# old_kick_line.net
KiCad netlist of a schematic drawn in EAGLE
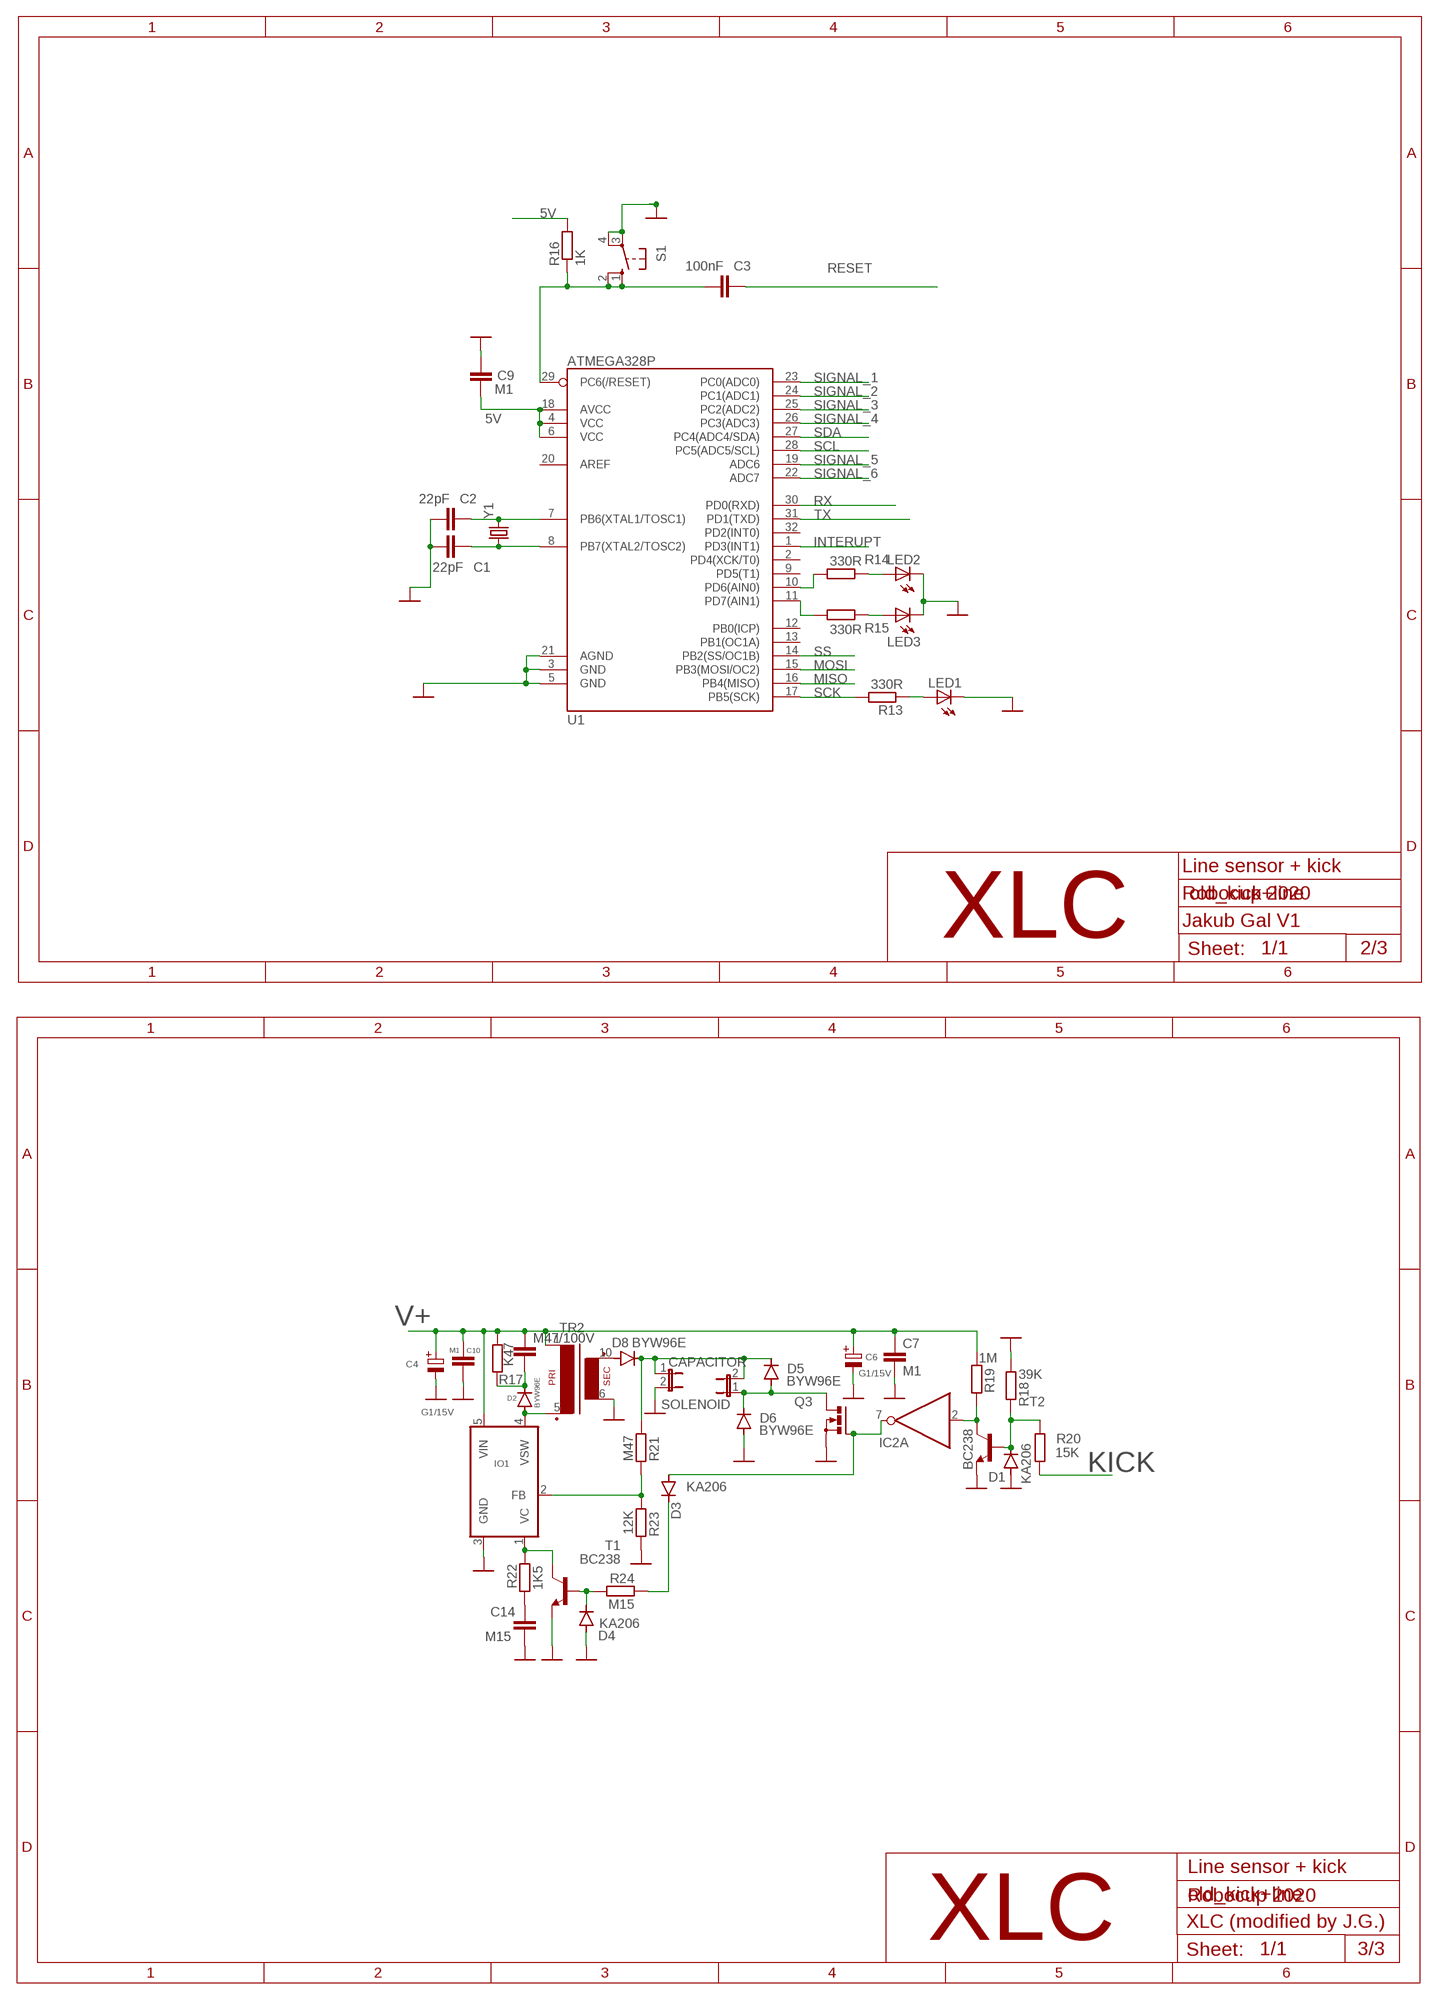
[diagram p0: schematic, sheet 1, part 1 of 2]
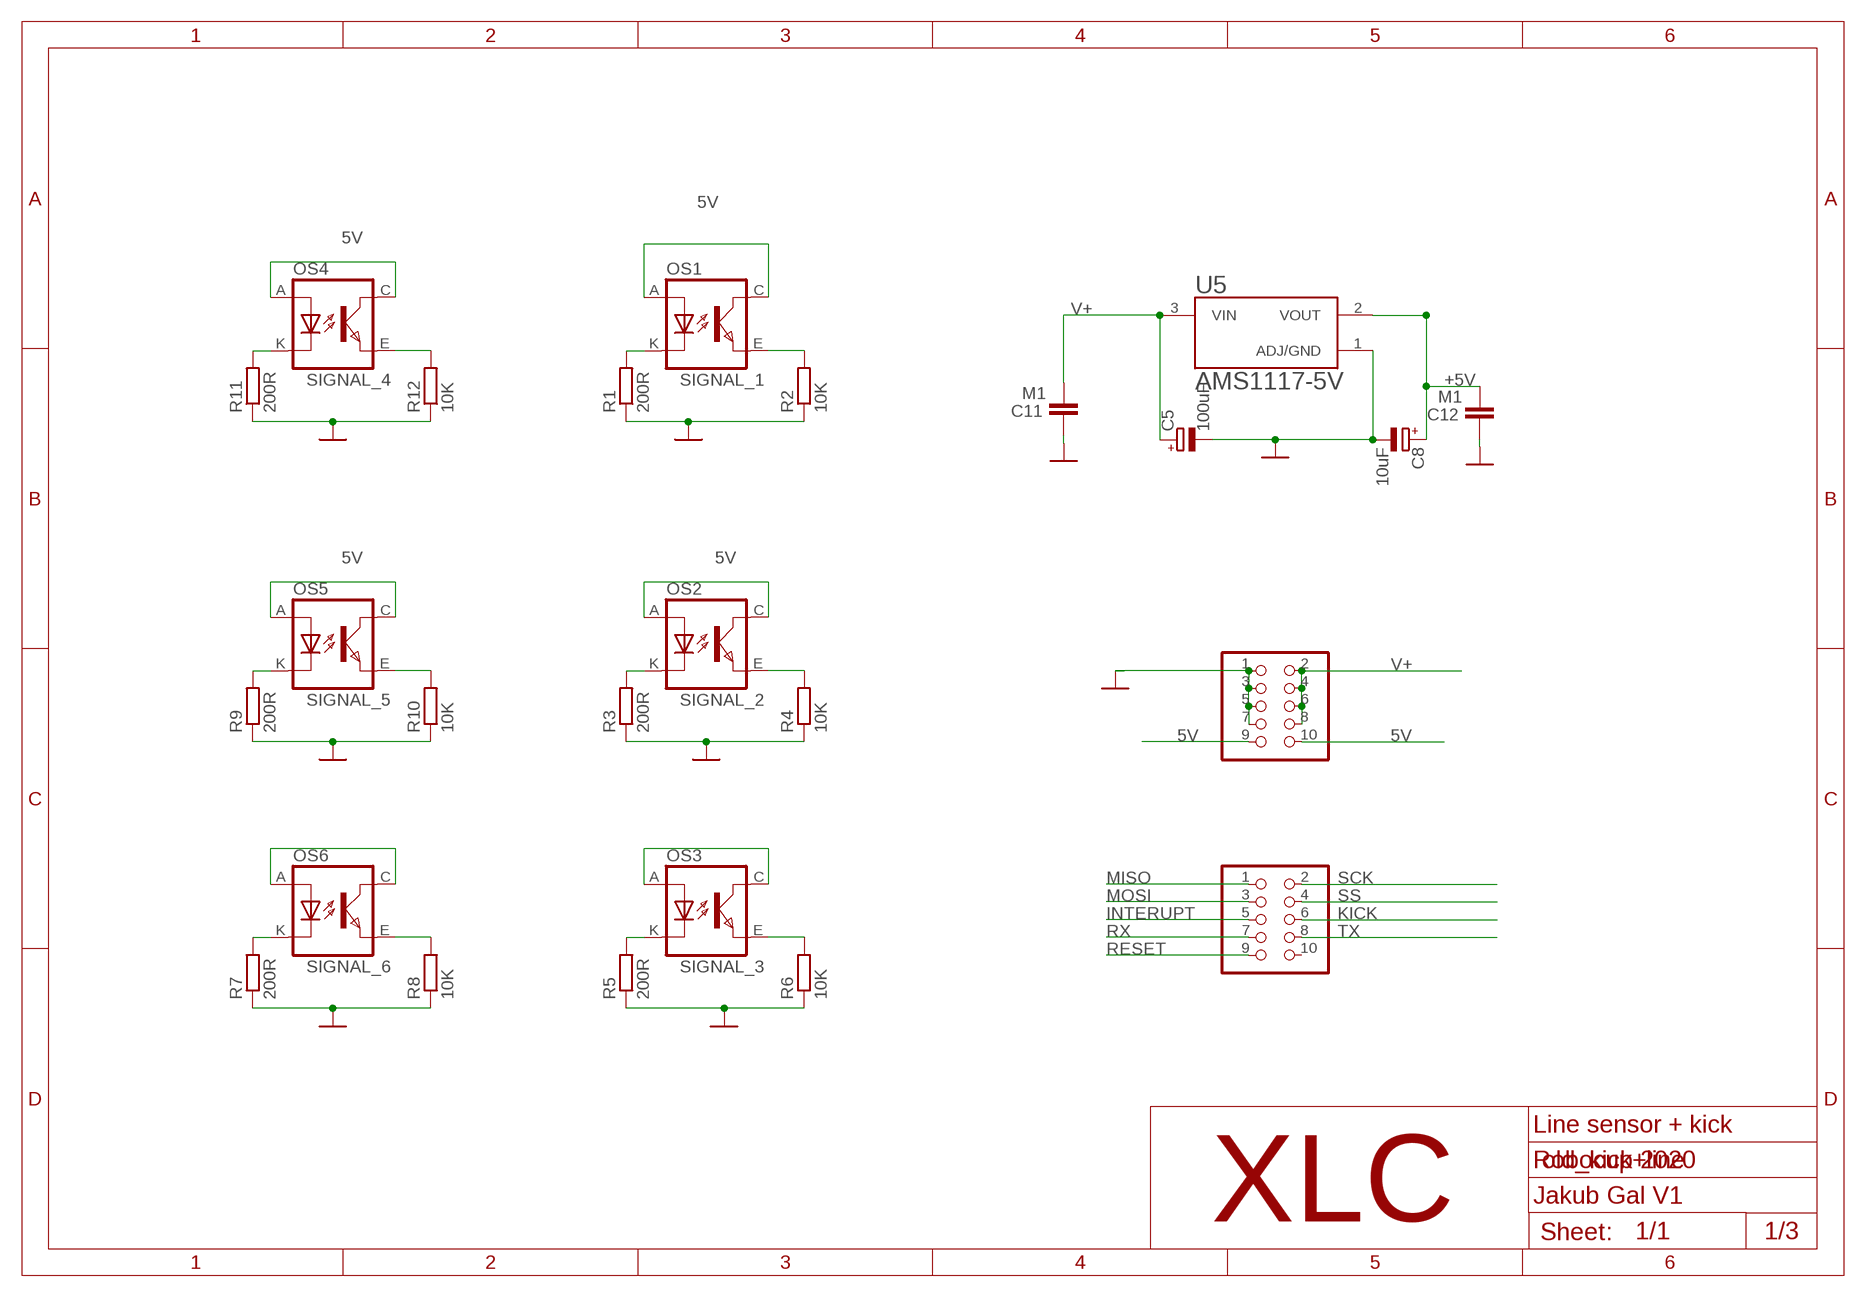
[diagram p1: schematic, sheet 1, part 2 of 2]

(export (version "E")
  (design (tool "Eeschema 10.0.6"))
  (components
    (comp (ref "C1")
      (value "22pF")
      (footprint "eagle-import:C0603")
      (libsource (lib "eagle-import") (part "C-EUC0603"))
    )
    (comp (ref "C2")
      (value "22pF")
      (footprint "eagle-import:C0603")
      (libsource (lib "eagle-import") (part "C-EUC0603"))
    )
    (comp (ref "C3")
      (value "100nF")
      (footprint "eagle-import:C0603")
      (libsource (lib "eagle-import") (part "C-EUC0603"))
    )
    (comp (ref "C4")
      (value "G1/15V")
      (footprint "eagle-import:E-2,5_7-RAD")
      (libsource (lib "eagle-import") (part "KOND-ELEKT-2,5/7"))
    )
    (comp (ref "C5")
      (value "100uF")
      (footprint "eagle-import:UD-6,3X7,7_NICHICON")
      (libsource (lib "eagle-import") (part "CPOL-EUUD-6,3X7,7"))
    )
    (comp (ref "C6")
      (value "G1/15V")
      (footprint "eagle-import:E-2,5_7-RAD")
      (libsource (lib "eagle-import") (part "KOND-ELEKT-2,5/7"))
    )
    (comp (ref "C7")
      (value "M1")
      (footprint "eagle-import:C0805K")
      (libsource (lib "eagle-import") (part "resistor_C-EUC0805K"))
    )
    (comp (ref "C8")
      (value "10uF")
      (footprint "eagle-import:UD-4X5,8_NICHICON")
      (libsource (lib "eagle-import") (part "CPOL-EUUD-4X5,8"))
    )
    (comp (ref "C9")
      (value "M1")
      (footprint "eagle-import:C0603")
      (libsource (lib "eagle-import") (part "C-EUC0603"))
    )
    (comp (ref "C10")
      (value "M1")
      (footprint "eagle-import:C0805K")
      (libsource (lib "eagle-import") (part "resistor_C-EUC0805K"))
    )
    (comp (ref "C11")
      (value "M1")
      (footprint "eagle-import:C0603")
      (libsource (lib "eagle-import") (part "C-EUC0603"))
    )
    (comp (ref "C12")
      (value "M1")
      (footprint "eagle-import:C0603")
      (libsource (lib "eagle-import") (part "C-EUC0603"))
    )
    (comp (ref "C14")
      (value "M15")
      (footprint "eagle-import:C0805K")
      (libsource (lib "eagle-import") (part "resistor_C-EUC0805K"))
    )
    (comp (ref "CAPACITOR")
      (value "JP1E")
      (footprint "eagle-import:JP1")
      (libsource (lib "eagle-import") (part "JP1E"))
    )
    (comp (ref "D1")
      (value "KA206")
      (footprint "eagle-import:D-7.5")
      (libsource (lib "eagle-import") (part "DIODE-D-7.5"))
    )
    (comp (ref "D2")
      (value "BYW96E")
      (footprint "eagle-import:SOD64-10")
      (libsource (lib "eagle-import") (part "BYW96"))
    )
    (comp (ref "D3")
      (value "KA206")
      (footprint "eagle-import:D-7.5")
      (libsource (lib "eagle-import") (part "DIODE-D-7.5"))
    )
    (comp (ref "D4")
      (value "KA206")
      (footprint "eagle-import:D-7.5")
      (libsource (lib "eagle-import") (part "DIODE-D-7.5"))
    )
    (comp (ref "D5")
      (value "BYW96E")
      (footprint "eagle-import:SOD64-10")
      (libsource (lib "eagle-import") (part "BYW96"))
    )
    (comp (ref "D6")
      (value "BYW96E")
      (footprint "eagle-import:SOD64-10")
      (libsource (lib "eagle-import") (part "BYW96"))
    )
    (comp (ref "D8")
      (value "BYW96E")
      (footprint "eagle-import:SOD64-10")
      (libsource (lib "eagle-import") (part "BYW96"))
    )
    (comp (ref "IC2")
      (value "MIC4423BM")
      (footprint "eagle-import:SO08")
      (libsource (lib "eagle-import") (part "MIC4423BM"))
    )
    (comp (ref "IO1")
      (value "LT1071V")
      (footprint "eagle-import:TO220-5P")
      (libsource (lib "eagle-import") (part "LT1071V"))
    )
    (comp (ref "JP2")
      (value "PINHD-2X5")
      (footprint "eagle-import:2X05")
      (libsource (lib "eagle-import") (part "PINHD-2X5"))
    )
    (comp (ref "JP3")
      (value "PINHD-2X5")
      (footprint "eagle-import:2X05")
      (libsource (lib "eagle-import") (part "PINHD-2X5"))
    )
    (comp (ref "LED1")
      (value "LEDCHIPLED_0603")
      (footprint "eagle-import:CHIPLED_0603")
      (libsource (lib "eagle-import") (part "LEDCHIPLED_0603"))
    )
    (comp (ref "LED2")
      (value "LEDCHIPLED_0603")
      (footprint "eagle-import:CHIPLED_0603")
      (libsource (lib "eagle-import") (part "LEDCHIPLED_0603"))
    )
    (comp (ref "LED3")
      (value "LEDCHIPLED_0603")
      (footprint "eagle-import:CHIPLED_0603")
      (libsource (lib "eagle-import") (part "LEDCHIPLED_0603"))
    )
    (comp (ref "M47/100V")
      (value "C-EUC0805K")
      (footprint "eagle-import:C0805K")
      (libsource (lib "eagle-import") (part "resistor_C-EUC0805K"))
    )
    (comp (ref "OS1")
      (value "TCRT5000")
      (footprint "eagle-import:TCRT5000")
      (libsource (lib "eagle-import") (part "TCRT5000"))
    )
    (comp (ref "OS2")
      (value "TCRT5000")
      (footprint "eagle-import:TCRT5000")
      (libsource (lib "eagle-import") (part "TCRT5000"))
    )
    (comp (ref "OS3")
      (value "TCRT5000")
      (footprint "eagle-import:TCRT5000")
      (libsource (lib "eagle-import") (part "TCRT5000"))
    )
    (comp (ref "OS4")
      (value "TCRT5000")
      (footprint "eagle-import:TCRT5000")
      (fields (field (name "SPICEPREFIX") "O"))
      (libsource (lib "eagle-import") (part "TCRT5000"))
    )
    (comp (ref "OS5")
      (value "TCRT5000")
      (footprint "eagle-import:TCRT5000")
      (libsource (lib "eagle-import") (part "TCRT5000"))
    )
    (comp (ref "OS6")
      (value "TCRT5000")
      (footprint "eagle-import:TCRT5000")
      (fields (field (name "SPICEPREFIX") "O"))
      (libsource (lib "eagle-import") (part "TCRT5000"))
    )
    (comp (ref "Q3")
      (value "PMOSFET_NTO220BV")
      (footprint "eagle-import:TO220BV")
      (libsource (lib "eagle-import") (part "PMOSFET_NTO220BV"))
    )
    (comp (ref "R1")
      (value "200R")
      (footprint "eagle-import:R0603")
      (libsource (lib "eagle-import") (part "R-EU_R0603"))
    )
    (comp (ref "R2")
      (value "10K")
      (footprint "eagle-import:R0603")
      (libsource (lib "eagle-import") (part "R-EU_R0603"))
    )
    (comp (ref "R3")
      (value "200R")
      (footprint "eagle-import:R0603")
      (libsource (lib "eagle-import") (part "R-EU_R0603"))
    )
    (comp (ref "R4")
      (value "10K")
      (footprint "eagle-import:R0603")
      (libsource (lib "eagle-import") (part "R-EU_R0603"))
    )
    (comp (ref "R5")
      (value "200R")
      (footprint "eagle-import:R0603")
      (libsource (lib "eagle-import") (part "R-EU_R0603"))
    )
    (comp (ref "R6")
      (value "10K")
      (footprint "eagle-import:R0603")
      (libsource (lib "eagle-import") (part "R-EU_R0603"))
    )
    (comp (ref "R7")
      (value "200R")
      (footprint "eagle-import:R0603")
      (libsource (lib "eagle-import") (part "R-EU_R0603"))
    )
    (comp (ref "R8")
      (value "10K")
      (footprint "eagle-import:R0603")
      (libsource (lib "eagle-import") (part "R-EU_R0603"))
    )
    (comp (ref "R9")
      (value "200R")
      (footprint "eagle-import:R0603")
      (libsource (lib "eagle-import") (part "R-EU_R0603"))
    )
    (comp (ref "R10")
      (value "10K")
      (footprint "eagle-import:R0603")
      (libsource (lib "eagle-import") (part "R-EU_R0603"))
    )
    (comp (ref "R11")
      (value "200R")
      (footprint "eagle-import:R0603")
      (libsource (lib "eagle-import") (part "R-EU_R0603"))
    )
    (comp (ref "R12")
      (value "10K")
      (footprint "eagle-import:R0603")
      (libsource (lib "eagle-import") (part "R-EU_R0603"))
    )
    (comp (ref "R13")
      (value "330R")
      (footprint "eagle-import:R0603")
      (libsource (lib "eagle-import") (part "R-EU_R0603"))
    )
    (comp (ref "R14")
      (value "330R")
      (footprint "eagle-import:R0603")
      (libsource (lib "eagle-import") (part "R-EU_R0603"))
    )
    (comp (ref "R15")
      (value "330R")
      (footprint "eagle-import:R0603")
      (libsource (lib "eagle-import") (part "R-EU_R0603"))
    )
    (comp (ref "R16")
      (value "1K")
      (footprint "eagle-import:R0603")
      (libsource (lib "eagle-import") (part "R-EU_R0603"))
    )
    (comp (ref "R17")
      (value "K47")
      (footprint "eagle-import:R0603")
      (libsource (lib "eagle-import") (part "resistor_R-EU_R0603"))
    )
    (comp (ref "R18")
      (value "39K")
      (footprint "eagle-import:R0603")
      (libsource (lib "eagle-import") (part "resistor_R-EU_R0603"))
    )
    (comp (ref "R19")
      (value "1M")
      (footprint "eagle-import:R0603")
      (libsource (lib "eagle-import") (part "resistor_R-EU_R0603"))
    )
    (comp (ref "R20")
      (value "15K")
      (footprint "eagle-import:R0603")
      (libsource (lib "eagle-import") (part "resistor_R-EU_R0603"))
    )
    (comp (ref "R21")
      (value "M47")
      (footprint "eagle-import:R0603")
      (libsource (lib "eagle-import") (part "resistor_R-EU_R0603"))
    )
    (comp (ref "R22")
      (value "1K5")
      (footprint "eagle-import:R0603")
      (libsource (lib "eagle-import") (part "resistor_R-EU_R0603"))
    )
    (comp (ref "R23")
      (value "12K")
      (footprint "eagle-import:R0603")
      (libsource (lib "eagle-import") (part "resistor_R-EU_R0603"))
    )
    (comp (ref "R24")
      (value "M15")
      (footprint "eagle-import:R0603")
      (libsource (lib "eagle-import") (part "resistor_R-EU_R0603"))
    )
    (comp (ref "S1")
      (value "10-XX")
      (footprint "eagle-import:B3F-10XX")
      (fields (field (name "MPN") "B3F-1000"))
      (libsource (lib "eagle-import") (part "10-XX"))
    )
    (comp (ref "SOLENOID")
      (value "JP1E")
      (footprint "eagle-import:JP1")
      (libsource (lib "eagle-import") (part "JP1E"))
    )
    (comp (ref "T1")
      (value "BC238")
      (footprint "eagle-import:TO92")
      (libsource (lib "eagle-import") (part "BC238"))
    )
    (comp (ref "T2")
      (value "BC238")
      (footprint "eagle-import:TO92")
      (libsource (lib "eagle-import") (part "BC238"))
    )
    (comp (ref "TR2")
      (value "TRAFO-E10-R\"\"")
      (footprint "eagle-import:TRAFO-EE17X20")
      (libsource (lib "eagle-import") (part "TRAFO-E10-R{dblquote}{dblquote}"))
    )
    (comp (ref "U1")
      (value "ATMEGA328P")
      (footprint "eagle-import:TQFP32-08")
      (libsource (lib "eagle-import") (part "ATMEGA328_SMT"))
    )
    (comp (ref "U5")
      (value "AMS1117-5V")
      (footprint "eagle-import:SOT229P700X180-4N")
      (fields (field (name "MF") "Advanced Monolithic Systems") (field (name "MP") "AMS1117-3.3"))
      (libsource (lib "eagle-import") (part "AMS1117-3.3"))
    )
    (comp (ref "Y1")
      (value "CRYSTALHC49US")
      (footprint "eagle-import:HC49US")
      (libsource (lib "eagle-import") (part "CRYSTALHC49US"))
    )
  )
  (nets
    (net (code "1") (name "/+5V") (class "Default")
      (node (ref "C12") (pin "1") (pinfunction "1_1") (pintype "passive"))
      (node (ref "C8") (pin "+") (pinfunction "+_+") (pintype "passive"))
      (node (ref "U5") (pin "2") (pinfunction "VOUT_2") (pintype "output"))
    )
    (net (code "2") (name "/5V") (class "Default")
      (node (ref "C9") (pin "1") (pinfunction "1_1") (pintype "passive"))
      (node (ref "JP3") (pin "10") (pinfunction "10_10") (pintype "passive"))
      (node (ref "JP3") (pin "9") (pinfunction "9_9") (pintype "passive"))
      (node (ref "OS1") (pin "A") (pinfunction "ANODE_A") (pintype "passive"))
      (node (ref "OS1") (pin "C") (pinfunction "COLLECTOR_C") (pintype "passive"))
      (node (ref "OS2") (pin "A") (pinfunction "ANODE_A") (pintype "passive"))
      (node (ref "OS2") (pin "C") (pinfunction "COLLECTOR_C") (pintype "passive"))
      (node (ref "OS3") (pin "A") (pinfunction "ANODE_A") (pintype "passive"))
      (node (ref "OS3") (pin "C") (pinfunction "COLLECTOR_C") (pintype "passive"))
      (node (ref "OS4") (pin "A") (pinfunction "ANODE_A") (pintype "passive"))
      (node (ref "OS4") (pin "C") (pinfunction "COLLECTOR_C") (pintype "passive"))
      (node (ref "OS5") (pin "A") (pinfunction "ANODE_A") (pintype "passive"))
      (node (ref "OS5") (pin "C") (pinfunction "COLLECTOR_C") (pintype "passive"))
      (node (ref "OS6") (pin "A") (pinfunction "ANODE_A") (pintype "passive"))
      (node (ref "OS6") (pin "C") (pinfunction "COLLECTOR_C") (pintype "passive"))
      (node (ref "R16") (pin "2") (pinfunction "2_2") (pintype "passive"))
      (node (ref "U1") (pin "18") (pinfunction "AVCC_18") (pintype "bidirectional"))
      (node (ref "U1") (pin "4") (pinfunction "VCC_4") (pintype "bidirectional"))
      (node (ref "U1") (pin "6") (pinfunction "VCC_6") (pintype "bidirectional"))
    )
    (net (code "3") (name "/INTERUPT") (class "Default")
      (node (ref "JP2") (pin "5") (pinfunction "5_5") (pintype "passive"))
      (node (ref "U1") (pin "1") (pinfunction "PD3(INT1)_1") (pintype "bidirectional"))
    )
    (net (code "4") (name "/KICK") (class "Default")
      (node (ref "JP2") (pin "6") (pinfunction "6_6") (pintype "passive"))
      (node (ref "R20") (pin "1") (pinfunction "1_1") (pintype "passive"))
    )
    (net (code "5") (name "/MISO") (class "Default")
      (node (ref "JP2") (pin "1") (pinfunction "1_1") (pintype "passive"))
      (node (ref "U1") (pin "16") (pinfunction "PB4(MISO)_16") (pintype "bidirectional"))
    )
    (net (code "6") (name "/MOSI") (class "Default")
      (node (ref "JP2") (pin "3") (pinfunction "3_3") (pintype "passive"))
      (node (ref "U1") (pin "15") (pinfunction "PB3(MOSI/OC2)_15") (pintype "bidirectional"))
    )
    (net (code "7") (name "/RESET") (class "Default")
      (node (ref "C3") (pin "2") (pinfunction "2_2") (pintype "passive"))
      (node (ref "JP2") (pin "9") (pinfunction "9_9") (pintype "passive"))
    )
    (net (code "8") (name "/RX") (class "Default")
      (node (ref "JP2") (pin "7") (pinfunction "7_7") (pintype "passive"))
      (node (ref "U1") (pin "30") (pinfunction "PD0(RXD)_30") (pintype "bidirectional"))
    )
    (net (code "9") (name "/SCK") (class "Default")
      (node (ref "JP2") (pin "2") (pinfunction "2_2") (pintype "passive"))
      (node (ref "R13") (pin "2") (pinfunction "2_2") (pintype "passive"))
      (node (ref "U1") (pin "17") (pinfunction "PB5(SCK)_17") (pintype "bidirectional"))
    )
    (net (code "10") (name "/SCL") (class "Default")
      (node (ref "U1") (pin "28") (pinfunction "PC5(ADC5/SCL)_28") (pintype "bidirectional"))
    )
    (net (code "11") (name "/SDA") (class "Default")
      (node (ref "U1") (pin "27") (pinfunction "PC4(ADC4/SDA)_27") (pintype "bidirectional"))
    )
    (net (code "12") (name "/SIGNAL_1") (class "Default")
      (node (ref "OS1") (pin "E") (pinfunction "EMITTER_E") (pintype "passive"))
      (node (ref "R2") (pin "2") (pinfunction "2_2") (pintype "passive"))
      (node (ref "U1") (pin "23") (pinfunction "PC0(ADC0)_23") (pintype "bidirectional"))
    )
    (net (code "13") (name "/SIGNAL_2") (class "Default")
      (node (ref "OS2") (pin "E") (pinfunction "EMITTER_E") (pintype "passive"))
      (node (ref "R4") (pin "2") (pinfunction "2_2") (pintype "passive"))
      (node (ref "U1") (pin "24") (pinfunction "PC1(ADC1)_24") (pintype "bidirectional"))
    )
    (net (code "14") (name "/SIGNAL_3") (class "Default")
      (node (ref "OS3") (pin "E") (pinfunction "EMITTER_E") (pintype "passive"))
      (node (ref "R6") (pin "2") (pinfunction "2_2") (pintype "passive"))
      (node (ref "U1") (pin "25") (pinfunction "PC2(ADC2)_25") (pintype "bidirectional"))
    )
    (net (code "15") (name "/SIGNAL_4") (class "Default")
      (node (ref "OS4") (pin "E") (pinfunction "EMITTER_E") (pintype "passive"))
      (node (ref "R12") (pin "2") (pinfunction "2_2") (pintype "passive"))
      (node (ref "U1") (pin "26") (pinfunction "PC3(ADC3)_26") (pintype "bidirectional"))
    )
    (net (code "16") (name "/SIGNAL_5") (class "Default")
      (node (ref "OS5") (pin "E") (pinfunction "EMITTER_E") (pintype "passive"))
      (node (ref "R10") (pin "2") (pinfunction "2_2") (pintype "passive"))
      (node (ref "U1") (pin "19") (pinfunction "ADC6_19") (pintype "bidirectional"))
    )
    (net (code "17") (name "/SIGNAL_6") (class "Default")
      (node (ref "OS6") (pin "E") (pinfunction "EMITTER_E") (pintype "passive"))
      (node (ref "R8") (pin "2") (pinfunction "2_2") (pintype "passive"))
      (node (ref "U1") (pin "22") (pinfunction "ADC7_22") (pintype "bidirectional"))
    )
    (net (code "18") (name "/SS") (class "Default")
      (node (ref "JP2") (pin "4") (pinfunction "4_4") (pintype "passive"))
      (node (ref "U1") (pin "14") (pinfunction "PB2(SS/OC1B)_14") (pintype "bidirectional"))
    )
    (net (code "19") (name "/TX") (class "Default")
      (node (ref "JP2") (pin "8") (pinfunction "8_8") (pintype "passive"))
      (node (ref "U1") (pin "31") (pinfunction "PD1(TXD)_31") (pintype "bidirectional"))
    )
    (net (code "20") (name "/V+") (class "Default")
      (node (ref "C10") (pin "1") (pinfunction "1_1") (pintype "passive"))
      (node (ref "C11") (pin "1") (pinfunction "1_1") (pintype "passive"))
      (node (ref "C4") (pin "+") (pinfunction "+_+") (pintype "passive"))
      (node (ref "C5") (pin "+") (pinfunction "+_+") (pintype "passive"))
      (node (ref "C6") (pin "+") (pinfunction "+_+") (pintype "passive"))
      (node (ref "C7") (pin "1") (pinfunction "1_1") (pintype "passive"))
      (node (ref "IO1") (pin "5") (pinfunction "VIN_5") (pintype "power_in"))
      (node (ref "JP3") (pin "2") (pinfunction "2_2") (pintype "passive"))
      (node (ref "JP3") (pin "4") (pinfunction "4_4") (pintype "passive"))
      (node (ref "JP3") (pin "6") (pinfunction "6_6") (pintype "passive"))
      (node (ref "JP3") (pin "8") (pinfunction "8_8") (pintype "passive"))
      (node (ref "M47/100V") (pin "1") (pinfunction "1_1") (pintype "passive"))
      (node (ref "R17") (pin "1") (pinfunction "1_1") (pintype "passive"))
      (node (ref "R19") (pin "2") (pinfunction "2_2") (pintype "passive"))
      (node (ref "TR2") (pin "1") (pinfunction "1_1") (pintype "passive"))
      (node (ref "U5") (pin "3") (pinfunction "VIN_3") (pintype "input"))
    )
    (net (code "21") (name "GND") (class "Default")
      (node (ref "C1") (pin "1") (pinfunction "1_1") (pintype "passive"))
      (node (ref "C10") (pin "2") (pinfunction "2_2") (pintype "passive"))
      (node (ref "C11") (pin "2") (pinfunction "2_2") (pintype "passive"))
      (node (ref "C12") (pin "2") (pinfunction "2_2") (pintype "passive"))
      (node (ref "C14") (pin "2") (pinfunction "2_2") (pintype "passive"))
      (node (ref "C2") (pin "1") (pinfunction "1_1") (pintype "passive"))
      (node (ref "C4") (pin "-") (pinfunction "-_-") (pintype "passive"))
      (node (ref "C5") (pin "-") (pinfunction "-_-") (pintype "passive"))
      (node (ref "C6") (pin "-") (pinfunction "-_-") (pintype "passive"))
      (node (ref "C7") (pin "2") (pinfunction "2_2") (pintype "passive"))
      (node (ref "C8") (pin "-") (pinfunction "-_-") (pintype "passive"))
      (node (ref "C9") (pin "2") (pinfunction "2_2") (pintype "passive"))
      (node (ref "CAPACITOR") (pin "2") (pinfunction "2_2") (pintype "passive"))
      (node (ref "D1") (pin "A") (pinfunction "A_A") (pintype "passive"))
      (node (ref "D4") (pin "A") (pinfunction "A_A") (pintype "passive"))
      (node (ref "D6") (pin "A") (pinfunction "A_A") (pintype "passive"))
      (node (ref "IO1") (pin "3") (pinfunction "GND_3") (pintype "power_in"))
      (node (ref "JP3") (pin "1") (pinfunction "1_1") (pintype "passive"))
      (node (ref "JP3") (pin "3") (pinfunction "3_3") (pintype "passive"))
      (node (ref "JP3") (pin "5") (pinfunction "5_5") (pintype "passive"))
      (node (ref "JP3") (pin "7") (pinfunction "7_7") (pintype "passive"))
      (node (ref "LED1") (pin "C") (pinfunction "C_C") (pintype "passive"))
      (node (ref "LED2") (pin "C") (pinfunction "C_C") (pintype "passive"))
      (node (ref "LED3") (pin "C") (pinfunction "C_C") (pintype "passive"))
      (node (ref "Q3") (pin "S") (pinfunction "S_S") (pintype "passive"))
      (node (ref "R1") (pin "1") (pinfunction "1_1") (pintype "passive"))
      (node (ref "R10") (pin "1") (pinfunction "1_1") (pintype "passive"))
      (node (ref "R11") (pin "1") (pinfunction "1_1") (pintype "passive"))
      (node (ref "R12") (pin "1") (pinfunction "1_1") (pintype "passive"))
      (node (ref "R18") (pin "2") (pinfunction "2_2") (pintype "passive"))
      (node (ref "R2") (pin "1") (pinfunction "1_1") (pintype "passive"))
      (node (ref "R23") (pin "1") (pinfunction "1_1") (pintype "passive"))
      (node (ref "R3") (pin "1") (pinfunction "1_1") (pintype "passive"))
      (node (ref "R4") (pin "1") (pinfunction "1_1") (pintype "passive"))
      (node (ref "R5") (pin "1") (pinfunction "1_1") (pintype "passive"))
      (node (ref "R6") (pin "1") (pinfunction "1_1") (pintype "passive"))
      (node (ref "R7") (pin "1") (pinfunction "1_1") (pintype "passive"))
      (node (ref "R8") (pin "1") (pinfunction "1_1") (pintype "passive"))
      (node (ref "R9") (pin "1") (pinfunction "1_1") (pintype "passive"))
      (node (ref "S1") (pin "3") (pinfunction "P_3") (pintype "passive"))
      (node (ref "S1") (pin "4") (pinfunction "P1_4") (pintype "passive"))
      (node (ref "T1") (pin "1") (pinfunction "E_1") (pintype "passive"))
      (node (ref "T2") (pin "1") (pinfunction "E_1") (pintype "passive"))
      (node (ref "TR2") (pin "6") (pinfunction "3_6") (pintype "passive"))
      (node (ref "U1") (pin "21") (pinfunction "AGND_21") (pintype "bidirectional"))
      (node (ref "U1") (pin "3") (pinfunction "GND_3") (pintype "bidirectional"))
      (node (ref "U1") (pin "5") (pinfunction "GND_5") (pintype "bidirectional"))
      (node (ref "U5") (pin "1") (pinfunction "ADJ/GND_1") (pintype "power_in"))
    )
    (net (code "22") (name "Net-(C14-Pad1)") (class "Default")
      (node (ref "C14") (pin "1") (pinfunction "1_1") (pintype "passive"))
      (node (ref "R22") (pin "2") (pinfunction "2_2") (pintype "passive"))
    )
    (net (code "23") (name "Net-(CAPACITOR-Pad1)") (class "Default")
      (node (ref "CAPACITOR") (pin "1") (pinfunction "1_1") (pintype "passive"))
      (node (ref "D5") (pin "C") (pinfunction "C_C") (pintype "passive"))
      (node (ref "D8") (pin "C") (pinfunction "C_C") (pintype "passive"))
      (node (ref "R21") (pin "2") (pinfunction "2_2") (pintype "passive"))
      (node (ref "SOLENOID") (pin "2") (pinfunction "2_2") (pintype "passive"))
    )
    (net (code "24") (name "Net-(D2-PadC)") (class "Default")
      (node (ref "D2") (pin "C") (pinfunction "C_C") (pintype "passive"))
      (node (ref "M47/100V") (pin "2") (pinfunction "2_2") (pintype "passive"))
      (node (ref "R17") (pin "2") (pinfunction "2_2") (pintype "passive"))
    )
    (net (code "25") (name "Net-(D3-PadC)") (class "Default")
      (node (ref "D3") (pin "C") (pinfunction "C_C") (pintype "passive"))
      (node (ref "R24") (pin "1") (pinfunction "1_1") (pintype "passive"))
    )
    (net (code "26") (name "Net-(D5-PadA)") (class "Default")
      (node (ref "D5") (pin "A") (pinfunction "A_A") (pintype "passive"))
      (node (ref "D6") (pin "C") (pinfunction "C_C") (pintype "passive"))
      (node (ref "Q3") (pin "D") (pinfunction "D_D") (pintype "passive"))
      (node (ref "SOLENOID") (pin "1") (pinfunction "1_1") (pintype "passive"))
    )
    (net (code "27") (name "Net-(IC2A-IN)") (class "Default")
      (node (ref "IC2") (pin "2") (pinfunction "IN_2") (pintype "input"))
      (node (ref "R19") (pin "1") (pinfunction "1_1") (pintype "passive"))
      (node (ref "T2") (pin "3") (pinfunction "C_3") (pintype "passive"))
    )
    (net (code "28") (name "Net-(IC2A-OUT)") (class "Default")
      (node (ref "D3") (pin "A") (pinfunction "A_A") (pintype "passive"))
      (node (ref "IC2") (pin "7") (pinfunction "OUT_7") (pintype "output"))
      (node (ref "Q3") (pin "G") (pinfunction "G_G") (pintype "passive"))
    )
    (net (code "29") (name "Net-(IO1-FB)") (class "Default")
      (node (ref "IO1") (pin "2") (pinfunction "FB_2") (pintype "input"))
      (node (ref "R21") (pin "1") (pinfunction "1_1") (pintype "passive"))
      (node (ref "R23") (pin "2") (pinfunction "2_2") (pintype "passive"))
    )
    (net (code "30") (name "Net-(IO1-VC)") (class "Default")
      (node (ref "IO1") (pin "1") (pinfunction "VC_1") (pintype "input"))
      (node (ref "R22") (pin "1") (pinfunction "1_1") (pintype "passive"))
      (node (ref "T1") (pin "3") (pinfunction "C_3") (pintype "passive"))
    )
    (net (code "31") (name "Net-(IO1-VSW)") (class "Default")
      (node (ref "D2") (pin "A") (pinfunction "A_A") (pintype "passive"))
      (node (ref "IO1") (pin "4") (pinfunction "VSW_4") (pintype "output"))
      (node (ref "TR2") (pin "5") (pinfunction "2_5") (pintype "passive"))
    )
    (net (code "32") (name "Net-(LED1-PadA)") (class "Default")
      (node (ref "LED1") (pin "A") (pinfunction "A_A") (pintype "passive"))
      (node (ref "R13") (pin "1") (pinfunction "1_1") (pintype "passive"))
    )
    (net (code "33") (name "Net-(LED2-PadA)") (class "Default")
      (node (ref "LED2") (pin "A") (pinfunction "A_A") (pintype "passive"))
      (node (ref "R14") (pin "1") (pinfunction "1_1") (pintype "passive"))
    )
    (net (code "34") (name "Net-(LED3-PadA)") (class "Default")
      (node (ref "LED3") (pin "A") (pinfunction "A_A") (pintype "passive"))
      (node (ref "R15") (pin "1") (pinfunction "1_1") (pintype "passive"))
    )
    (net (code "35") (name "Net-(OS1-CATHODE)") (class "Default")
      (node (ref "OS1") (pin "K") (pinfunction "CATHODE_K") (pintype "passive"))
      (node (ref "R1") (pin "2") (pinfunction "2_2") (pintype "passive"))
    )
    (net (code "36") (name "Net-(OS2-CATHODE)") (class "Default")
      (node (ref "OS2") (pin "K") (pinfunction "CATHODE_K") (pintype "passive"))
      (node (ref "R3") (pin "2") (pinfunction "2_2") (pintype "passive"))
    )
    (net (code "37") (name "Net-(OS3-CATHODE)") (class "Default")
      (node (ref "OS3") (pin "K") (pinfunction "CATHODE_K") (pintype "passive"))
      (node (ref "R5") (pin "2") (pinfunction "2_2") (pintype "passive"))
    )
    (net (code "38") (name "Net-(OS4-CATHODE)") (class "Default")
      (node (ref "OS4") (pin "K") (pinfunction "CATHODE_K") (pintype "passive"))
      (node (ref "R11") (pin "2") (pinfunction "2_2") (pintype "passive"))
    )
    (net (code "39") (name "Net-(OS5-CATHODE)") (class "Default")
      (node (ref "OS5") (pin "K") (pinfunction "CATHODE_K") (pintype "passive"))
      (node (ref "R9") (pin "2") (pinfunction "2_2") (pintype "passive"))
    )
    (net (code "40") (name "Net-(OS6-CATHODE)") (class "Default")
      (node (ref "OS6") (pin "K") (pinfunction "CATHODE_K") (pintype "passive"))
      (node (ref "R7") (pin "2") (pinfunction "2_2") (pintype "passive"))
    )
    (net (code "41") (name "Net-(S1-S)") (class "Default")
      (node (ref "C3") (pin "1") (pinfunction "1_1") (pintype "passive"))
      (node (ref "R16") (pin "1") (pinfunction "1_1") (pintype "passive"))
      (node (ref "S1") (pin "1") (pinfunction "S_1") (pintype "passive"))
      (node (ref "S1") (pin "2") (pinfunction "S1_2") (pintype "passive"))
      (node (ref "U1") (pin "29") (pinfunction "PC6(/RESET)_29") (pintype "bidirectional"))
    )
    (net (code "42") (name "Net-(T1-B)") (class "Default")
      (node (ref "D4") (pin "C") (pinfunction "C_C") (pintype "passive"))
      (node (ref "R24") (pin "2") (pinfunction "2_2") (pintype "passive"))
      (node (ref "T1") (pin "2") (pinfunction "B_2") (pintype "passive"))
    )
    (net (code "43") (name "Net-(T2-B)") (class "Default")
      (node (ref "D1") (pin "C") (pinfunction "C_C") (pintype "passive"))
      (node (ref "R18") (pin "1") (pinfunction "1_1") (pintype "passive"))
      (node (ref "R20") (pin "2") (pinfunction "2_2") (pintype "passive"))
      (node (ref "T2") (pin "2") (pinfunction "B_2") (pintype "passive"))
    )
    (net (code "44") (name "Net-(TR2-4)") (class "Default")
      (node (ref "D8") (pin "A") (pinfunction "A_A") (pintype "passive"))
      (node (ref "TR2") (pin "10") (pinfunction "4_10") (pintype "passive"))
    )
    (net (code "45") (name "Net-(U1-PB6(XTAL1{slash}TOSC1))") (class "Default")
      (node (ref "C2") (pin "2") (pinfunction "2_2") (pintype "passive"))
      (node (ref "U1") (pin "7") (pinfunction "PB6(XTAL1/TOSC1)_7") (pintype "bidirectional"))
      (node (ref "Y1") (pin "2") (pinfunction "2_2") (pintype "passive"))
    )
    (net (code "46") (name "Net-(U1-PB7(XTAL2{slash}TOSC2))") (class "Default")
      (node (ref "C1") (pin "2") (pinfunction "2_2") (pintype "passive"))
      (node (ref "U1") (pin "8") (pinfunction "PB7(XTAL2/TOSC2)_8") (pintype "bidirectional"))
      (node (ref "Y1") (pin "1") (pinfunction "1_1") (pintype "passive"))
    )
    (net (code "47") (name "Net-(U1-PD6(AIN0))") (class "Default")
      (node (ref "R14") (pin "2") (pinfunction "2_2") (pintype "passive"))
      (node (ref "U1") (pin "10") (pinfunction "PD6(AIN0)_10") (pintype "bidirectional"))
    )
    (net (code "48") (name "Net-(U1-PD7(AIN1))") (class "Default")
      (node (ref "R15") (pin "2") (pinfunction "2_2") (pintype "passive"))
      (node (ref "U1") (pin "11") (pinfunction "PD7(AIN1)_11") (pintype "bidirectional"))
    )
    (net (code "49") (name "unconnected-(JP2-Pad10)") (class "Default")
      (node (ref "JP2") (pin "10") (pinfunction "10_10") (pintype "passive"))
    )
    (net (code "50") (name "unconnected-(U1-AREF-Pad20)") (class "Default")
      (node (ref "U1") (pin "20") (pinfunction "AREF_20") (pintype "bidirectional"))
    )
    (net (code "51") (name "unconnected-(U1-PB0(ICP)-Pad12)") (class "Default")
      (node (ref "U1") (pin "12") (pinfunction "PB0(ICP)_12") (pintype "bidirectional"))
    )
    (net (code "52") (name "unconnected-(U1-PB1(OC1A)-Pad13)") (class "Default")
      (node (ref "U1") (pin "13") (pinfunction "PB1(OC1A)_13") (pintype "bidirectional"))
    )
    (net (code "53") (name "unconnected-(U1-PD2(INT0)-Pad32)") (class "Default")
      (node (ref "U1") (pin "32") (pinfunction "PD2(INT0)_32") (pintype "bidirectional"))
    )
    (net (code "54") (name "unconnected-(U1-PD4(XCK{slash}T0)-Pad2)") (class "Default")
      (node (ref "U1") (pin "2") (pinfunction "PD4(XCK/T0)_2") (pintype "bidirectional"))
    )
    (net (code "55") (name "unconnected-(U1-PD5(T1)-Pad9)") (class "Default")
      (node (ref "U1") (pin "9") (pinfunction "PD5(T1)_9") (pintype "bidirectional"))
    )
  )
)
